# ETH_PHY.net
KiCad netlist of a schematic drawn in Altium Designer
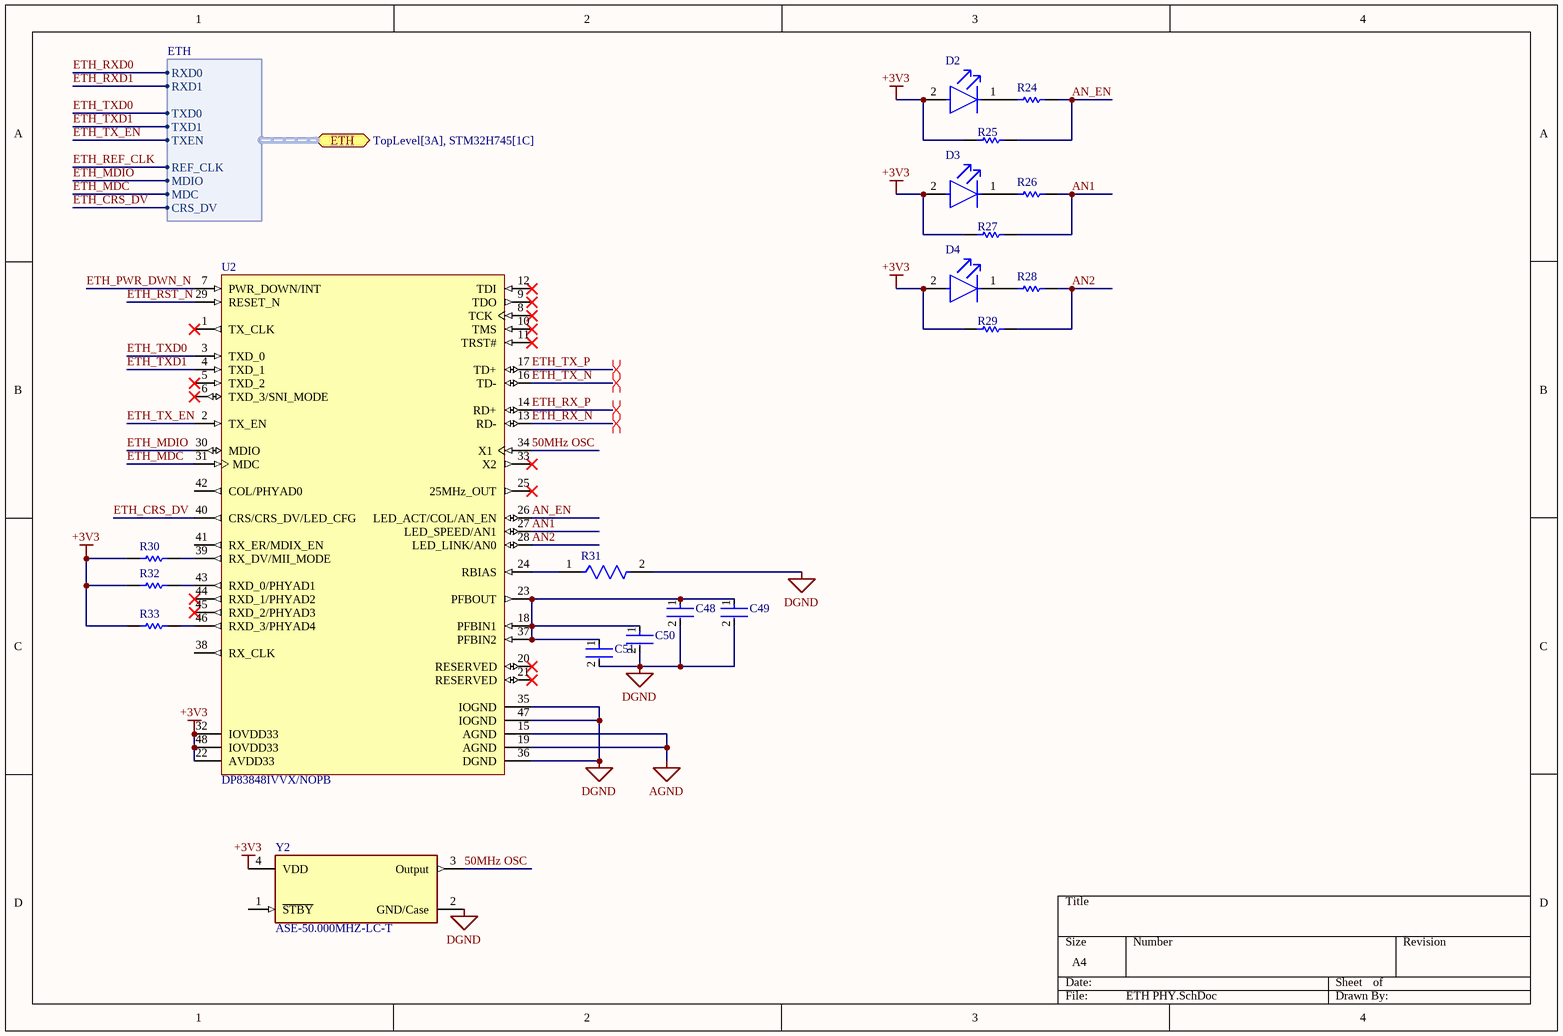
[diagram p0: ETH PHY.SchDoc]

(export (version "E")
  (design (tool "Eeschema 10.0.6"))
  (components
    (comp (ref "C48")
      (value "GRM188R61A106KE69J")
      (footprint "FP-GRM188-0_15-MFG")
      (description "CAP CER 10UF 10V X5R 0603")
      (fields (field (name "TOLERANCE") "10%"))
      (libsource (lib "Altium Content Vault") (part "b4654b650e69147ec39a6b967a45e02"))
    )
    (comp (ref "C49")
      (value "CL05A104JO5NNNC")
      (footprint "FP-CL45-IPC_C")
      (description "Cap Ceramic 100nF 16V X5R ±5% SMD 0402 +85°C Paper T/R")
      (fields (field (name "TOLERANCE") "5%"))
      (libsource (lib "Altium Content Vault") (part "b4654b650e69147ec39a6b967a45e02"))
    )
    (comp (ref "C50")
      (value "CL05A104JO5NNNC")
      (footprint "FP-CL45-IPC_C")
      (description "Cap Ceramic 100nF 16V X5R ±5% SMD 0402 +85°C Paper T/R")
      (fields (field (name "TOLERANCE") "5%"))
      (libsource (lib "Altium Content Vault") (part "b4654b650e69147ec39a6b967a45e02"))
    )
    (comp (ref "C51")
      (value "CL05A104JO5NNNC")
      (footprint "FP-CL45-IPC_C")
      (description "Cap Ceramic 100nF 16V X5R ±5% SMD 0402 +85°C Paper T/R")
      (fields (field (name "TOLERANCE") "5%"))
      (libsource (lib "Altium Content Vault") (part "b4654b650e69147ec39a6b967a45e02"))
    )
    (comp (ref "D2")
      (value "APHD1608LZGCK")
      (footprint "FP-APHD1608LZGCK-MFG")
      (description "LED GREEN CLEAR 1608 SMD")
      (libsource (lib "Altium Content Vault") (part "8706943c75ba83719d021d2fdc84c58"))
    )
    (comp (ref "D3")
      (value "APHD1608LZGCK")
      (footprint "FP-APHD1608LZGCK-MFG")
      (description "LED GREEN CLEAR 1608 SMD")
      (libsource (lib "Altium Content Vault") (part "8706943c75ba83719d021d2fdc84c58"))
    )
    (comp (ref "D4")
      (value "APHD1608LZGCK")
      (footprint "FP-APHD1608LZGCK-MFG")
      (description "LED GREEN CLEAR 1608 SMD")
      (libsource (lib "Altium Content Vault") (part "8706943c75ba83719d021d2fdc84c58"))
    )
    (comp (ref "R24")
      (value "CRCW0603110RFKEA")
      (footprint "RESC1609X50X30NL10T20")
      (fields (field (name "MANUFACTURER") "Vishay Dale"))
      (libsource (lib "Altium Content Vault") (part "RES"))
    )
    (comp (ref "R25")
      (value "RC0402JR-072K2L")
      (footprint "RESC1005X40X25NL5T10")
      (description "Chip Resistor, 2.2 KOhm, +/- 5%, 0.063 W, -55 to 155 degC, 0402 (1005 Metric), RoHS, Tape and Reel")
      (fields (field (name "TOLERANCE") "5%"))
      (libsource (lib "Altium Content Vault") (part "RES-2"))
    )
    (comp (ref "R26")
      (value "CRCW0603110RFKEA")
      (footprint "RESC1609X50X30NL10T20")
      (fields (field (name "MANUFACTURER") "Vishay Dale"))
      (libsource (lib "Altium Content Vault") (part "RES"))
    )
    (comp (ref "R27")
      (value "RC0402JR-072K2L")
      (footprint "RESC1005X40X25NL5T10")
      (description "Chip Resistor, 2.2 KOhm, +/- 5%, 0.063 W, -55 to 155 degC, 0402 (1005 Metric), RoHS, Tape and Reel")
      (fields (field (name "TOLERANCE") "5%"))
      (libsource (lib "Altium Content Vault") (part "RES-2"))
    )
    (comp (ref "R28")
      (value "CRCW0603110RFKEA")
      (footprint "RESC1609X50X30NL10T20")
      (fields (field (name "MANUFACTURER") "Vishay Dale"))
      (libsource (lib "Altium Content Vault") (part "RES"))
    )
    (comp (ref "R29")
      (value "RC0402JR-072K2L")
      (footprint "RESC1005X40X25NL5T10")
      (description "Chip Resistor, 2.2 KOhm, +/- 5%, 0.063 W, -55 to 155 degC, 0402 (1005 Metric), RoHS, Tape and Reel")
      (fields (field (name "TOLERANCE") "5%"))
      (libsource (lib "Altium Content Vault") (part "RES-2"))
    )
    (comp (ref "R30")
      (value "RC0402JR-072K2L")
      (footprint "RESC1005X40X25NL5T10")
      (description "Chip Resistor, 2.2 KOhm, +/- 5%, 0.063 W, -55 to 155 degC, 0402 (1005 Metric), RoHS, Tape and Reel")
      (fields (field (name "TOLERANCE") "5%"))
      (libsource (lib "Altium Content Vault") (part "RES-2"))
    )
    (comp (ref "R31")
      (value "RK73H1JTTD4871D")
      (footprint "FP-RK73H1J-IPC_C")
      (description "4.87kΩ ±0.5% 0.1W Chip Resistor 0603 Thick Film AEC-Q200 Qualified")
      (libsource (lib "Altium Content Vault") (part "1029c3af85768c4190bb7ad29bc67b5"))
    )
    (comp (ref "R32")
      (value "RC0402JR-072K2L")
      (footprint "RESC1005X40X25NL5T10")
      (description "Chip Resistor, 2.2 KOhm, +/- 5%, 0.063 W, -55 to 155 degC, 0402 (1005 Metric), RoHS, Tape and Reel")
      (fields (field (name "TOLERANCE") "5%"))
      (libsource (lib "Altium Content Vault") (part "RES-2"))
    )
    (comp (ref "R33")
      (value "RC0402JR-072K2L")
      (footprint "RESC1005X40X25NL5T10")
      (description "Chip Resistor, 2.2 KOhm, +/- 5%, 0.063 W, -55 to 155 degC, 0402 (1005 Metric), RoHS, Tape and Reel")
      (fields (field (name "TOLERANCE") "5%"))
      (libsource (lib "Altium Content Vault") (part "RES-2"))
    )
    (comp (ref "U2")
      (value "DP83848IVVX/NOPB")
      (footprint "PT0048A_L")
      (fields (field (name "MANUFACTURER") "Texas Instruments"))
      (libsource (lib "Altium Content Vault") (part "IN-LNTX-DP83848IVV"))
    )
    (comp (ref "Y2")
      (value "ASE-50.000MHZ-LC-T")
      (footprint "FP-ASE-MFG")
      (description "XTAL Oscillator 50MHz ±50ppm CMOS 3.3V 4-SMD 3.2mm x 2.5mm")
      (libsource (lib "Altium Content Vault") (part "61a724e6190563596ac712fef61ad37"))
    )
  )
  (nets
    (net (code "2") (name "+3V3") (class "Default")
      (node (ref "D2") (pin "2") (pinfunction "A_2") (pintype "passive"))
      (node (ref "D3") (pin "2") (pinfunction "A_2") (pintype "passive"))
      (node (ref "D4") (pin "2") (pinfunction "A_2") (pintype "passive"))
      (node (ref "R25") (pin "2") (pinfunction "2_2") (pintype "passive"))
      (node (ref "R27") (pin "2") (pinfunction "2_2") (pintype "passive"))
      (node (ref "R29") (pin "2") (pinfunction "2_2") (pintype "passive"))
      (node (ref "R30") (pin "2") (pinfunction "2_2") (pintype "passive"))
      (node (ref "R32") (pin "2") (pinfunction "2_2") (pintype "passive"))
      (node (ref "R33") (pin "2") (pinfunction "2_2") (pintype "passive"))
      (node (ref "U2") (pin "22") (pinfunction "AVDD33_22") (pintype "power_in"))
      (node (ref "U2") (pin "32") (pinfunction "IOVDD33_32") (pintype "power_in"))
      (node (ref "U2") (pin "48") (pinfunction "IOVDD33_48") (pintype "power_in"))
      (node (ref "Y2") (pin "4") (pinfunction "VDD_4") (pintype "power_in"))
    )
    (net (code "3") (name "/50MHz OSC") (class "Default")
      (node (ref "U2") (pin "34") (pinfunction "X1_34") (pintype "input"))
      (node (ref "Y2") (pin "3") (pinfunction "Output_3") (pintype "output"))
    )
    (net (code "4") (name "/AN1") (class "Default")
      (node (ref "R26") (pin "2") (pinfunction "2_2") (pintype "passive"))
      (node (ref "R27") (pin "1") (pinfunction "1_1") (pintype "passive"))
      (node (ref "U2") (pin "27") (pinfunction "LED_SPEED/AN1_27") (pintype "bidirectional"))
    )
    (net (code "5") (name "/AN2") (class "Default")
      (node (ref "R28") (pin "2") (pinfunction "2_2") (pintype "passive"))
      (node (ref "R29") (pin "1") (pinfunction "1_1") (pintype "passive"))
      (node (ref "U2") (pin "28") (pinfunction "LED_LINK/AN0_28") (pintype "bidirectional"))
    )
    (net (code "6") (name "/AN_EN") (class "Default")
      (node (ref "R24") (pin "2") (pinfunction "2_2") (pintype "passive"))
      (node (ref "R25") (pin "1") (pinfunction "1_1") (pintype "passive"))
      (node (ref "U2") (pin "26") (pinfunction "LED_ACT/COL/AN_EN_26") (pintype "bidirectional"))
    )
    (net (code "7") (name "/ETH_CRS_DV") (class "Default")
      (node (ref "U2") (pin "40") (pinfunction "CRS/CRS_DV/LED_CFG_40") (pintype "output"))
    )
    (net (code "8") (name "/ETH_MDC") (class "Default")
      (node (ref "U2") (pin "31") (pinfunction "MDC_31") (pintype "input"))
    )
    (net (code "9") (name "/ETH_MDIO") (class "Default")
      (node (ref "U2") (pin "30") (pinfunction "MDIO_30") (pintype "bidirectional"))
    )
    (net (code "10") (name "/ETH_PWR_DWN_N") (class "Default")
      (node (ref "U2") (pin "7") (pinfunction "PWR_DOWN/INT_7") (pintype "input"))
    )
    (net (code "12") (name "/ETH_RST_N") (class "Default")
      (node (ref "U2") (pin "29") (pinfunction "RESET_N_29") (pintype "input"))
    )
    (net (code "15") (name "/ETH_RX_N") (class "Default")
      (node (ref "U2") (pin "13") (pinfunction "RD-_13") (pintype "bidirectional"))
    )
    (net (code "16") (name "/ETH_RX_P") (class "Default")
      (node (ref "U2") (pin "14") (pinfunction "RD+_14") (pintype "bidirectional"))
    )
    (net (code "17") (name "/ETH_TXD0") (class "Default")
      (node (ref "U2") (pin "3") (pinfunction "TXD_0_3") (pintype "input"))
    )
    (net (code "18") (name "/ETH_TXD1") (class "Default")
      (node (ref "U2") (pin "4") (pinfunction "TXD_1_4") (pintype "input"))
    )
    (net (code "19") (name "/ETH_TX_EN") (class "Default")
      (node (ref "U2") (pin "2") (pinfunction "TX_EN_2") (pintype "input"))
    )
    (net (code "20") (name "/ETH_TX_N") (class "Default")
      (node (ref "U2") (pin "16") (pinfunction "TD-_16") (pintype "bidirectional"))
    )
    (net (code "21") (name "/ETH_TX_P") (class "Default")
      (node (ref "U2") (pin "17") (pinfunction "TD+_17") (pintype "bidirectional"))
    )
    (net (code "23") (name "AGND") (class "Default")
      (node (ref "U2") (pin "15") (pinfunction "AGND_15") (pintype "power_in"))
      (node (ref "U2") (pin "19") (pinfunction "AGND_19") (pintype "power_in"))
    )
    (net (code "24") (name "DGND") (class "Default")
      (node (ref "C48") (pin "2") (pinfunction "2_2") (pintype "passive"))
      (node (ref "C49") (pin "2") (pinfunction "2_2") (pintype "passive"))
      (node (ref "C50") (pin "2") (pinfunction "2_2") (pintype "passive"))
      (node (ref "C51") (pin "2") (pinfunction "2_2") (pintype "passive"))
      (node (ref "R31") (pin "2") (pinfunction "2_2") (pintype "passive"))
      (node (ref "U2") (pin "35") (pinfunction "IOGND_35") (pintype "power_in"))
      (node (ref "U2") (pin "36") (pinfunction "DGND_36") (pintype "power_in"))
      (node (ref "U2") (pin "47") (pinfunction "IOGND_47") (pintype "power_in"))
      (node (ref "Y2") (pin "2") (pinfunction "GND/Case_2") (pintype "power_in"))
    )
    (net (code "25") (name "Net-(D2-C)") (class "Default")
      (node (ref "D2") (pin "1") (pinfunction "C_1") (pintype "passive"))
      (node (ref "R24") (pin "1") (pinfunction "1_1") (pintype "passive"))
    )
    (net (code "26") (name "Net-(D3-C)") (class "Default")
      (node (ref "D3") (pin "1") (pinfunction "C_1") (pintype "passive"))
      (node (ref "R26") (pin "1") (pinfunction "1_1") (pintype "passive"))
    )
    (net (code "27") (name "Net-(D4-C)") (class "Default")
      (node (ref "D4") (pin "1") (pinfunction "C_1") (pintype "passive"))
      (node (ref "R28") (pin "1") (pinfunction "1_1") (pintype "passive"))
    )
    (net (code "28") (name "Net-(U2-PFBIN1)") (class "Default")
      (node (ref "C48") (pin "1") (pinfunction "1_1") (pintype "passive"))
      (node (ref "C49") (pin "1") (pinfunction "1_1") (pintype "passive"))
      (node (ref "C50") (pin "1") (pinfunction "1_1") (pintype "passive"))
      (node (ref "C51") (pin "1") (pinfunction "1_1") (pintype "passive"))
      (node (ref "U2") (pin "18") (pinfunction "PFBIN1_18") (pintype "input"))
      (node (ref "U2") (pin "23") (pinfunction "PFBOUT_23") (pintype "output"))
      (node (ref "U2") (pin "37") (pinfunction "PFBIN2_37") (pintype "input"))
    )
    (net (code "29") (name "Net-(U2-RBIAS)") (class "Default")
      (node (ref "R31") (pin "1") (pinfunction "1_1") (pintype "passive"))
      (node (ref "U2") (pin "24") (pinfunction "RBIAS_24") (pintype "input"))
    )
    (net (code "30") (name "Net-(U2-RXD_0{slash}PHYAD1)") (class "Default")
      (node (ref "R32") (pin "1") (pinfunction "1_1") (pintype "passive"))
      (node (ref "U2") (pin "43") (pinfunction "RXD_0/PHYAD1_43") (pintype "output"))
    )
    (net (code "31") (name "Net-(U2-RXD_3{slash}PHYAD4)") (class "Default")
      (node (ref "R33") (pin "1") (pinfunction "1_1") (pintype "passive"))
      (node (ref "U2") (pin "46") (pinfunction "RXD_3/PHYAD4_46") (pintype "output"))
    )
    (net (code "32") (name "Net-(U2-RX_DV{slash}MII_MODE)") (class "Default")
      (node (ref "R30") (pin "1") (pinfunction "1_1") (pintype "passive"))
      (node (ref "U2") (pin "39") (pinfunction "RX_DV/MII_MODE_39") (pintype "output"))
    )
    (net (code "33") (name "unconnected-(U2-25MHz_OUT-Pad25)") (class "Default")
      (node (ref "U2") (pin "25") (pinfunction "25MHz_OUT_25") (pintype "output+no_connect"))
    )
    (net (code "34") (name "unconnected-(U2-COL{slash}PHYAD0-Pad42)") (class "Default")
      (node (ref "U2") (pin "42") (pinfunction "COL/PHYAD0_42") (pintype "output"))
    )
    (net (code "35") (name "unconnected-(U2-RESERVED-Pad20)") (class "Default")
      (node (ref "U2") (pin "20") (pinfunction "RESERVED_20") (pintype "bidirectional+no_connect"))
    )
    (net (code "36") (name "unconnected-(U2-RESERVED-Pad21)") (class "Default")
      (node (ref "U2") (pin "21") (pinfunction "RESERVED_21") (pintype "bidirectional+no_connect"))
    )
    (net (code "37") (name "unconnected-(U2-RXD_1{slash}PHYAD2-Pad44)") (class "Default")
      (node (ref "U2") (pin "44") (pinfunction "RXD_1/PHYAD2_44") (pintype "output+no_connect"))
    )
    (net (code "38") (name "unconnected-(U2-RXD_2{slash}PHYAD3-Pad45)") (class "Default")
      (node (ref "U2") (pin "45") (pinfunction "RXD_2/PHYAD3_45") (pintype "output+no_connect"))
    )
    (net (code "39") (name "unconnected-(U2-RX_CLK-Pad38)") (class "Default")
      (node (ref "U2") (pin "38") (pinfunction "RX_CLK_38") (pintype "output"))
    )
    (net (code "40") (name "unconnected-(U2-RX_ER{slash}MDIX_EN-Pad41)") (class "Default")
      (node (ref "U2") (pin "41") (pinfunction "RX_ER/MDIX_EN_41") (pintype "output"))
    )
    (net (code "41") (name "unconnected-(U2-TCK-Pad8)") (class "Default")
      (node (ref "U2") (pin "8") (pinfunction "TCK_8") (pintype "input+no_connect"))
    )
    (net (code "42") (name "unconnected-(U2-TDI-Pad12)") (class "Default")
      (node (ref "U2") (pin "12") (pinfunction "TDI_12") (pintype "input+no_connect"))
    )
    (net (code "43") (name "unconnected-(U2-TDO-Pad9)") (class "Default")
      (node (ref "U2") (pin "9") (pinfunction "TDO_9") (pintype "output+no_connect"))
    )
    (net (code "44") (name "unconnected-(U2-TMS-Pad10)") (class "Default")
      (node (ref "U2") (pin "10") (pinfunction "TMS_10") (pintype "input+no_connect"))
    )
    (net (code "45") (name "unconnected-(U2-TRST#-Pad11)") (class "Default")
      (node (ref "U2") (pin "11") (pinfunction "TRST#_11") (pintype "input+no_connect"))
    )
    (net (code "46") (name "unconnected-(U2-TXD_2-Pad5)") (class "Default")
      (node (ref "U2") (pin "5") (pinfunction "TXD_2_5") (pintype "input+no_connect"))
    )
    (net (code "47") (name "unconnected-(U2-TXD_3{slash}SNI_MODE-Pad6)") (class "Default")
      (node (ref "U2") (pin "6") (pinfunction "TXD_3/SNI_MODE_6") (pintype "bidirectional+no_connect"))
    )
    (net (code "48") (name "unconnected-(U2-TX_CLK-Pad1)") (class "Default")
      (node (ref "U2") (pin "1") (pinfunction "TX_CLK_1") (pintype "output+no_connect"))
    )
    (net (code "49") (name "unconnected-(U2-X2-Pad33)") (class "Default")
      (node (ref "U2") (pin "33") (pinfunction "X2_33") (pintype "output+no_connect"))
    )
    (net (code "50") (name "unconnected-(Y2-~{STBY}-Pad1)") (class "Default")
      (node (ref "Y2") (pin "1") (pinfunction "~{STBY}_1") (pintype "input"))
    )
  )
)
